# SCH_PowerSupply7805.net
KiCad netlist of a schematic drawn in Altium Designer
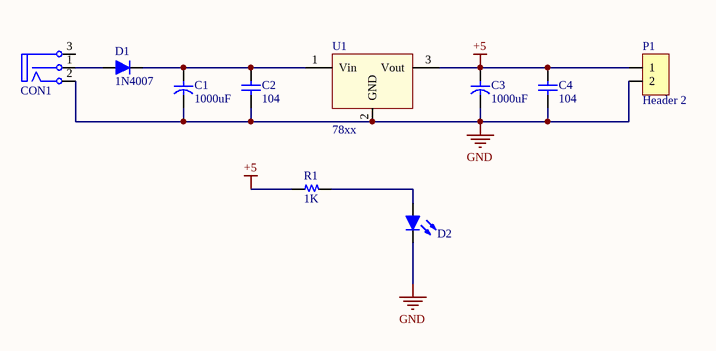
[diagram p0: SCH_PowerSupply7805.SchDoc]

(export (version "E")
  (design (tool "Eeschema 10.0.6"))
  (components
    (comp (ref "C1")
      (value "1000uF")
      (footprint "CYL/D.400/LS.200")
      (description "Capacitor pol")
      (libsource (lib "chipfc_altium_libs") (part "Capacitor"))
    )
    (comp (ref "C2")
      (value "104")
      (footprint "CAP Ceramic/W300")
      (description "Capacitor non-pol")
      (libsource (lib "chipfc_altium_libs") (part "Capacitor NP"))
    )
    (comp (ref "C3")
      (value "1000uF")
      (footprint "CYL/D.400/LS.200")
      (description "Capacitor pol")
      (libsource (lib "chipfc_altium_libs") (part "Capacitor"))
    )
    (comp (ref "C4")
      (value "104")
      (footprint "CAP Ceramic/W300")
      (description "Capacitor non-pol")
      (libsource (lib "chipfc_altium_libs") (part "Capacitor NP"))
    )
    (comp (ref "CON1")
      (value "CON DC PWR")
      (footprint "CONN/DC/PWR/5.0MM")
      (description "DC input connector")
      (libsource (lib "chipfc_altium_libs") (part "CON DC PWR"))
    )
    (comp (ref "D1")
      (value "1N4007")
      (footprint "DO-41")
      (description "Default Diode")
      (libsource (lib "chipfc_altium_libs") (part "Diode"))
    )
    (comp (ref "D2")
      (value "Led")
      (footprint "LED 5MM - RED")
      (description "Typical LED")
      (libsource (lib "chipfc_altium_libs") (part "Led"))
    )
    (comp (ref "P1")
      (value "Header 2")
      (footprint "HDR/Terminal/2")
      (description "Header, 2-Pin")
      (libsource (lib "chipfc_altium_libs") (part "Header 2"))
    )
    (comp (ref "R1")
      (value "1K")
      (footprint "R 1/4W/300")
      (description "Resistor")
      (libsource (lib "chipfc_altium_libs") (part "Resistor"))
    )
    (comp (ref "U1")
      (value "78xx")
      (footprint "TO-220")
      (description "LDO Fixed Voltage regulator")
      (libsource (lib "chipfc_altium_libs") (part "78xx"))
    )
  )
  (nets
    (net (code "1") (name "+5") (class "Default")
      (node (ref "C3") (pin "1") (pinfunction "1_1") (pintype "passive"))
      (node (ref "C4") (pin "1") (pinfunction "1_1") (pintype "passive"))
      (node (ref "P1") (pin "1") (pinfunction "1_1") (pintype "passive"))
      (node (ref "R1") (pin "1") (pinfunction "1_1") (pintype "passive"))
      (node (ref "U1") (pin "3") (pinfunction "Vout_3") (pintype "passive"))
    )
    (net (code "2") (name "GND") (class "Default")
      (node (ref "C1") (pin "2") (pinfunction "2_2") (pintype "passive"))
      (node (ref "C2") (pin "2") (pinfunction "2_2") (pintype "passive"))
      (node (ref "C3") (pin "2") (pinfunction "2_2") (pintype "passive"))
      (node (ref "C4") (pin "2") (pinfunction "2_2") (pintype "passive"))
      (node (ref "CON1") (pin "2") (pinfunction "T_2") (pintype "passive"))
      (node (ref "D2") (pin "2") (pinfunction "K_2") (pintype "passive"))
      (node (ref "P1") (pin "2") (pinfunction "2_2") (pintype "passive"))
      (node (ref "U1") (pin "2") (pinfunction "GND_2") (pintype "passive"))
    )
    (net (code "3") (name "Net-(CON1-S)") (class "Default")
      (node (ref "CON1") (pin "1") (pinfunction "S_1") (pintype "power_in"))
      (node (ref "D1") (pin "1") (pinfunction "A_1") (pintype "passive"))
    )
    (net (code "4") (name "Net-(D1-K)") (class "Default")
      (node (ref "C1") (pin "1") (pinfunction "1_1") (pintype "passive"))
      (node (ref "C2") (pin "1") (pinfunction "1_1") (pintype "passive"))
      (node (ref "D1") (pin "2") (pinfunction "K_2") (pintype "passive"))
      (node (ref "U1") (pin "1") (pinfunction "Vin_1") (pintype "power_in"))
    )
    (net (code "5") (name "Net-(D2-A)") (class "Default")
      (node (ref "D2") (pin "1") (pinfunction "A_1") (pintype "passive"))
      (node (ref "R1") (pin "2") (pinfunction "2_2") (pintype "passive"))
    )
    (net (code "6") (name "unconnected-(CON1-TN-Pad3)") (class "Default")
      (node (ref "CON1") (pin "3") (pinfunction "TN_3") (pintype "passive"))
    )
  )
)
